# Main_Board_SW2.net
KiCad netlist of a schematic drawn in EAGLE
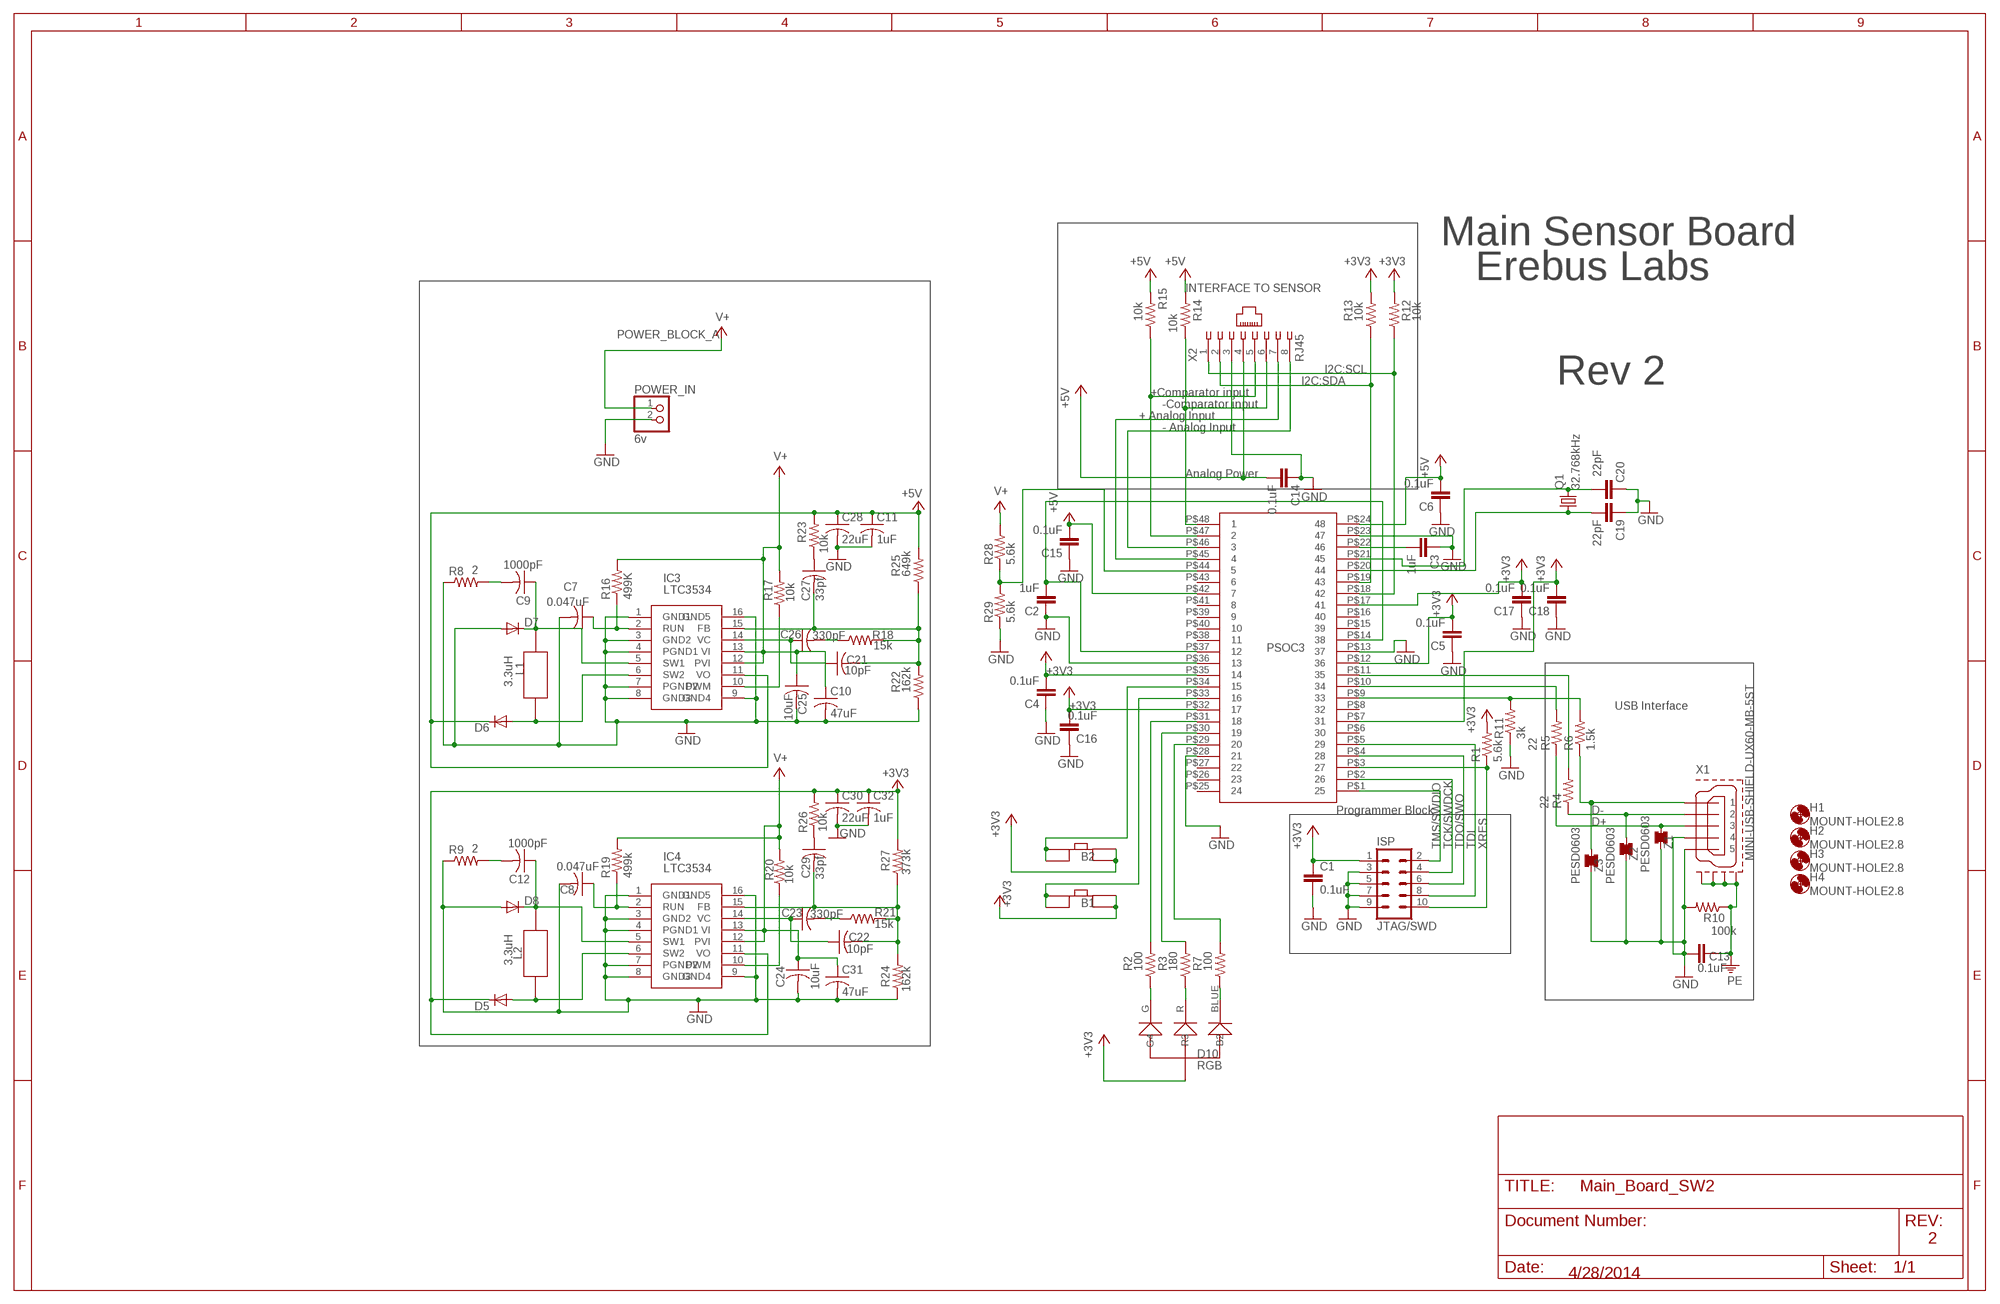
[diagram p0: schematic, sheet 1]

(export (version "E")
  (design (tool "Eeschema 10.0.6"))
  (components
    (comp (ref "C1")
      (value "0.1uF")
      (footprint "eagle-import:C0603K")
      (libsource (lib "eagle-import") (part "C-EUC0603K"))
    )
    (comp (ref "C2")
      (value "1uF")
      (footprint "eagle-import:C0603")
      (libsource (lib "eagle-import") (part "C-EUC0603"))
    )
    (comp (ref "C3")
      (value "1uF")
      (footprint "eagle-import:C0603")
      (libsource (lib "eagle-import") (part "C-EUC0603"))
    )
    (comp (ref "C4")
      (value "0.1uF")
      (footprint "eagle-import:C0603K")
      (libsource (lib "eagle-import") (part "C-EUC0603K"))
    )
    (comp (ref "C5")
      (value "0.1uF")
      (footprint "eagle-import:C0603K")
      (libsource (lib "eagle-import") (part "C-EUC0603K"))
    )
    (comp (ref "C6")
      (value "0.1uF")
      (footprint "eagle-import:C0603K")
      (libsource (lib "eagle-import") (part "C-EUC0603K"))
    )
    (comp (ref "C7")
      (value "0.047uF")
      (footprint "eagle-import:C0402")
      (libsource (lib "eagle-import") (part "C-USC0402"))
    )
    (comp (ref "C8")
      (value "0.047uF")
      (footprint "eagle-import:C0402")
      (libsource (lib "eagle-import") (part "C-USC0402"))
    )
    (comp (ref "C9")
      (value "1000pF")
      (footprint "eagle-import:C0402")
      (libsource (lib "eagle-import") (part "C-USC0402"))
    )
    (comp (ref "C10")
      (value "47uF")
      (footprint "eagle-import:C1210")
      (libsource (lib "eagle-import") (part "C-USC1210"))
    )
    (comp (ref "C11")
      (value "1uF")
      (footprint "eagle-import:C0603")
      (libsource (lib "eagle-import") (part "C-USC0603"))
    )
    (comp (ref "C12")
      (value "1000pF")
      (footprint "eagle-import:C0402")
      (libsource (lib "eagle-import") (part "C-USC0402"))
    )
    (comp (ref "C13")
      (value "0.1uF")
      (footprint "eagle-import:C0603K")
      (libsource (lib "eagle-import") (part "C-EUC0603K"))
    )
    (comp (ref "C14")
      (value "0.1uF")
      (footprint "eagle-import:C0603K")
      (libsource (lib "eagle-import") (part "C-EUC0603K"))
    )
    (comp (ref "C15")
      (value "0.1uF")
      (footprint "eagle-import:C0603K")
      (libsource (lib "eagle-import") (part "C-EUC0603K"))
    )
    (comp (ref "C16")
      (value "0.1uF")
      (footprint "eagle-import:C0603K")
      (libsource (lib "eagle-import") (part "C-EUC0603K"))
    )
    (comp (ref "C17")
      (value "0.1uF")
      (footprint "eagle-import:C0603K")
      (libsource (lib "eagle-import") (part "C-EUC0603K"))
    )
    (comp (ref "C18")
      (value "0.1uF")
      (footprint "eagle-import:C0603K")
      (libsource (lib "eagle-import") (part "C-EUC0603K"))
    )
    (comp (ref "C19")
      (value "22pF")
      (footprint "eagle-import:C0603")
      (libsource (lib "eagle-import") (part "C-EUC0603"))
    )
    (comp (ref "C20")
      (value "22pF")
      (footprint "eagle-import:C0603")
      (libsource (lib "eagle-import") (part "C-EUC0603"))
    )
    (comp (ref "C21")
      (value "10pF")
      (footprint "eagle-import:C0805")
      (libsource (lib "eagle-import") (part "C-USC0805"))
    )
    (comp (ref "C22")
      (value "10pF")
      (footprint "eagle-import:C0805")
      (libsource (lib "eagle-import") (part "C-USC0805"))
    )
    (comp (ref "C23")
      (value "330pF")
      (footprint "eagle-import:C0805")
      (libsource (lib "eagle-import") (part "C-USC0805"))
    )
    (comp (ref "C24")
      (value "10uF")
      (footprint "eagle-import:C0805")
      (libsource (lib "eagle-import") (part "C-USC0805"))
    )
    (comp (ref "C25")
      (value "10uF")
      (footprint "eagle-import:C0805")
      (libsource (lib "eagle-import") (part "C-USC0805"))
    )
    (comp (ref "C26")
      (value "330pF")
      (footprint "eagle-import:C0805")
      (libsource (lib "eagle-import") (part "C-USC0805"))
    )
    (comp (ref "C27")
      (value "33pf")
      (footprint "eagle-import:C0805")
      (libsource (lib "eagle-import") (part "C-USC0805"))
    )
    (comp (ref "C28")
      (value "22uF")
      (footprint "eagle-import:C0805")
      (libsource (lib "eagle-import") (part "C-USC0805"))
    )
    (comp (ref "C29")
      (value "33pf")
      (footprint "eagle-import:C0805")
      (libsource (lib "eagle-import") (part "C-USC0805"))
    )
    (comp (ref "C30")
      (value "22uF")
      (footprint "eagle-import:C0805")
      (libsource (lib "eagle-import") (part "C-USC0805"))
    )
    (comp (ref "C31")
      (value "47uF")
      (footprint "eagle-import:C1210")
      (libsource (lib "eagle-import") (part "C-USC1210"))
    )
    (comp (ref "C32")
      (value "1uF")
      (footprint "eagle-import:C0603")
      (libsource (lib "eagle-import") (part "C-USC0603"))
    )
    (comp (ref "D5")
      (value "DIODE-SOD323-R")
      (footprint "eagle-import:SOD323-R")
      (libsource (lib "eagle-import") (part "DIODE-SOD323-R"))
    )
    (comp (ref "D6")
      (value "DIODE-SOD323-R")
      (footprint "eagle-import:SOD323-R")
      (libsource (lib "eagle-import") (part "DIODE-SOD323-R"))
    )
    (comp (ref "D7")
      (value "DIODE-SOD323-R")
      (footprint "eagle-import:SOD323-R")
      (libsource (lib "eagle-import") (part "DIODE-SOD323-R"))
    )
    (comp (ref "D8")
      (value "DIODE-SOD323-R")
      (footprint "eagle-import:SOD323-R")
      (libsource (lib "eagle-import") (part "DIODE-SOD323-R"))
    )
    (comp (ref "H1")
      (value "MOUNT-HOLE2.8")
      (footprint "eagle-import:2,8")
      (libsource (lib "eagle-import") (part "MOUNT-HOLE2.8"))
    )
    (comp (ref "H2")
      (value "MOUNT-HOLE2.8")
      (footprint "eagle-import:2,8")
      (libsource (lib "eagle-import") (part "MOUNT-HOLE2.8"))
    )
    (comp (ref "H3")
      (value "MOUNT-HOLE2.8")
      (footprint "eagle-import:2,8")
      (libsource (lib "eagle-import") (part "MOUNT-HOLE2.8"))
    )
    (comp (ref "H4")
      (value "MOUNT-HOLE2.8")
      (footprint "eagle-import:2,8")
      (libsource (lib "eagle-import") (part "MOUNT-HOLE2.8"))
    )
    (comp (ref "IC3")
      (value "SWITCHER")
      (footprint "eagle-import:SSOP16")
      (libsource (lib "eagle-import") (part "SWITCHER"))
    )
    (comp (ref "IC4")
      (value "SWITCHER")
      (footprint "eagle-import:SSOP16")
      (libsource (lib "eagle-import") (part "SWITCHER"))
    )
    (comp (ref "ISP")
      (value "JTAG/SWD")
      (footprint "eagle-import:FTSH-105-01-L-DV-K")
      (libsource (lib "eagle-import") (part "FTSH-105-01-L-DV-K"))
    )
    (comp (ref "L1")
      (value "3.3uH")
      (footprint "eagle-import:SHEILDED_COIL")
      (libsource (lib "eagle-import") (part "SHEILDED_COIL"))
    )
    (comp (ref "L2")
      (value "4.7uH")
      (footprint "eagle-import:SHEILDED_COIL")
      (libsource (lib "eagle-import") (part "SHEILDED_COIL"))
    )
    (comp (ref "POWER_IN")
      (value "6v")
      (footprint "eagle-import:1X02")
      (libsource (lib "eagle-import") (part "PINHD-1X2"))
    )
    (comp (ref "Q1")
      (value "32.768kHz")
      (footprint "eagle-import:TC38H")
      (libsource (lib "eagle-import") (part "CRYSTALTC38H"))
    )
    (comp (ref "R1")
      (value "5.6k")
      (footprint "eagle-import:R0805")
      (libsource (lib "eagle-import") (part "R-US_R0805"))
    )
    (comp (ref "R2")
      (value "100")
      (footprint "eagle-import:R0805")
      (libsource (lib "eagle-import") (part "R-US_R0805"))
    )
    (comp (ref "R3")
      (value "180")
      (footprint "eagle-import:R0805")
      (libsource (lib "eagle-import") (part "R-US_R0805"))
    )
    (comp (ref "R4")
      (value "22")
      (footprint "eagle-import:R0603")
      (libsource (lib "eagle-import") (part "R-US_R0603"))
    )
    (comp (ref "R5")
      (value "22")
      (footprint "eagle-import:R0603")
      (libsource (lib "eagle-import") (part "R-US_R0603"))
    )
    (comp (ref "R6")
      (value "1.5k")
      (footprint "eagle-import:R0805")
      (libsource (lib "eagle-import") (part "R-US_R0805"))
    )
    (comp (ref "R7")
      (value "100")
      (footprint "eagle-import:R0805")
      (libsource (lib "eagle-import") (part "R-US_R0805"))
    )
    (comp (ref "R8")
      (value "2")
      (footprint "eagle-import:R0402")
      (libsource (lib "eagle-import") (part "R-US_R0402"))
    )
    (comp (ref "R9")
      (value "2")
      (footprint "eagle-import:R0402")
      (libsource (lib "eagle-import") (part "R-US_R0402"))
    )
    (comp (ref "R10")
      (value "100k")
      (footprint "eagle-import:R0805")
      (libsource (lib "eagle-import") (part "R-US_R0805"))
    )
    (comp (ref "R11")
      (value "3k")
      (footprint "eagle-import:R0805")
      (libsource (lib "eagle-import") (part "R-US_R0805"))
    )
    (comp (ref "R12")
      (value "10k")
      (footprint "eagle-import:R0805")
      (libsource (lib "eagle-import") (part "R-US_R0805"))
    )
    (comp (ref "R13")
      (value "10k")
      (footprint "eagle-import:R0805")
      (libsource (lib "eagle-import") (part "R-US_R0805"))
    )
    (comp (ref "R14")
      (value "10k")
      (footprint "eagle-import:R0805")
      (libsource (lib "eagle-import") (part "R-US_R0805"))
    )
    (comp (ref "R15")
      (value "10k")
      (footprint "eagle-import:R0805")
      (libsource (lib "eagle-import") (part "R-US_R0805"))
    )
    (comp (ref "R16")
      (value "499K")
      (footprint "eagle-import:R0805")
      (libsource (lib "eagle-import") (part "resistor_R-US_R0805"))
    )
    (comp (ref "R17")
      (value "10k")
      (footprint "eagle-import:R0805")
      (libsource (lib "eagle-import") (part "R-US_R0805"))
    )
    (comp (ref "R18")
      (value "15k")
      (footprint "eagle-import:R0805")
      (libsource (lib "eagle-import") (part "R-US_R0805"))
    )
    (comp (ref "R19")
      (value "499k")
      (footprint "eagle-import:R0805")
      (libsource (lib "eagle-import") (part "resistor_R-US_R0805"))
    )
    (comp (ref "R20")
      (value "10k")
      (footprint "eagle-import:R0805")
      (libsource (lib "eagle-import") (part "R-US_R0805"))
    )
    (comp (ref "R21")
      (value "15k")
      (footprint "eagle-import:R0805")
      (libsource (lib "eagle-import") (part "R-US_R0805"))
    )
    (comp (ref "R22")
      (value "162k")
      (footprint "eagle-import:R0805")
      (libsource (lib "eagle-import") (part "R-US_R0805"))
    )
    (comp (ref "R23")
      (value "10k")
      (footprint "eagle-import:R0805")
      (libsource (lib "eagle-import") (part "R-US_R0805"))
    )
    (comp (ref "R24")
      (value "162k")
      (footprint "eagle-import:R0805")
      (libsource (lib "eagle-import") (part "R-US_R0805"))
    )
    (comp (ref "R25")
      (value "649k")
      (footprint "eagle-import:R0805")
      (libsource (lib "eagle-import") (part "R-US_R0805"))
    )
    (comp (ref "R26")
      (value "10k")
      (footprint "eagle-import:R0805")
      (libsource (lib "eagle-import") (part "R-US_R0805"))
    )
    (comp (ref "R27")
      (value "373k")
      (footprint "eagle-import:R0805")
      (libsource (lib "eagle-import") (part "R-US_R0805"))
    )
    (comp (ref "R28")
      (value "5.6k")
      (footprint "eagle-import:R0805")
      (libsource (lib "eagle-import") (part "R-US_R0805"))
    )
    (comp (ref "R29")
      (value "5.6k")
      (footprint "eagle-import:R0805")
      (libsource (lib "eagle-import") (part "R-US_R0805"))
    )
    (comp (ref "RGB_LED")
      (value "RGB_LED")
      (footprint "eagle-import:RGB_LED")
      (libsource (lib "eagle-import") (part "RGB_LED"))
    )
    (comp (ref "U$1")
      (value "PSOC_3_48PIN_SSOP")
      (footprint "eagle-import:PSOC_3_48PIN_SSOP")
      (libsource (lib "eagle-import") (part "PSOC_3_48PIN_SSOP"))
    )
    (comp (ref "U$5")
      (value "SPST")
      (footprint "eagle-import:SPST")
      (libsource (lib "eagle-import") (part "SPST"))
    )
    (comp (ref "U$6")
      (value "SPST")
      (footprint "eagle-import:SPST")
      (libsource (lib "eagle-import") (part "SPST"))
    )
    (comp (ref "X1")
      (value "MINI-USB-SHIELD-UX60-MB-5ST")
      (footprint "eagle-import:UX60-MB-5ST")
      (libsource (lib "eagle-import") (part "MINI-USB-SHIELD-UX60-MB-5ST"))
    )
    (comp (ref "X2")
      (value "RJ45")
      (footprint "eagle-import:555167-1")
      (libsource (lib "eagle-import") (part "555167-1"))
    )
    (comp (ref "Z1")
      (value "PESD0603")
      (footprint "eagle-import:SMD-0603")
      (libsource (lib "eagle-import") (part "PESD0603"))
    )
    (comp (ref "Z2")
      (value "PESD0603")
      (footprint "eagle-import:SMD-0603")
      (libsource (lib "eagle-import") (part "PESD0603"))
    )
    (comp (ref "Z3")
      (value "PESD0603")
      (footprint "eagle-import:SMD-0603")
      (libsource (lib "eagle-import") (part "PESD0603"))
    )
  )
  (nets
    (net (code "1") (name "+3V3") (class "Default")
      (node (ref "C1") (pin "1") (pinfunction "1_1") (pintype "passive"))
      (node (ref "C16") (pin "2") (pinfunction "2_2") (pintype "passive"))
      (node (ref "C17") (pin "2") (pinfunction "2_2") (pintype "passive"))
      (node (ref "C18") (pin "2") (pinfunction "2_2") (pintype "passive"))
      (node (ref "C30") (pin "1") (pinfunction "1_1") (pintype "passive"))
      (node (ref "C32") (pin "1") (pinfunction "1_1") (pintype "passive"))
      (node (ref "C4") (pin "2") (pinfunction "2_2") (pintype "passive"))
      (node (ref "C5") (pin "2") (pinfunction "2_2") (pintype "passive"))
      (node (ref "D5") (pin "C") (pinfunction "C_C") (pintype "passive"))
      (node (ref "IC4") (pin "11") (pinfunction "VO_11") (pintype "bidirectional"))
      (node (ref "ISP") (pin "1") (pinfunction "1_1") (pintype "passive"))
      (node (ref "R1") (pin "2") (pinfunction "2_2") (pintype "passive"))
      (node (ref "R12") (pin "2") (pinfunction "2_2") (pintype "passive"))
      (node (ref "R13") (pin "2") (pinfunction "2_2") (pintype "passive"))
      (node (ref "R26") (pin "2") (pinfunction "2_2") (pintype "passive"))
      (node (ref "R27") (pin "2") (pinfunction "2_2") (pintype "passive"))
      (node (ref "RGB_LED") (pin "VCC") (pinfunction "VCC1_VCC") (pintype "bidirectional"))
      (node (ref "U$1") (pin "P$12") (pinfunction "36_P$12") (pintype "bidirectional"))
      (node (ref "U$1") (pin "P$17") (pinfunction "41_P$17") (pintype "bidirectional"))
      (node (ref "U$1") (pin "P$32") (pinfunction "17_P$32") (pintype "bidirectional"))
      (node (ref "U$1") (pin "P$35") (pinfunction "14_P$35") (pintype "bidirectional"))
      (node (ref "U$1") (pin "P$7") (pinfunction "31_P$7") (pintype "bidirectional"))
      (node (ref "U$5") (pin "B1") (pinfunction "B1_B1") (pintype "bidirectional"))
      (node (ref "U$5") (pin "B2") (pinfunction "B2_B2") (pintype "bidirectional"))
      (node (ref "U$6") (pin "B1") (pinfunction "B1_B1") (pintype "bidirectional"))
      (node (ref "U$6") (pin "B2") (pinfunction "B2_B2") (pintype "bidirectional"))
    )
    (net (code "2") (name "+5V") (class "Default")
      (node (ref "C11") (pin "1") (pinfunction "1_1") (pintype "passive"))
      (node (ref "C14") (pin "2") (pinfunction "2_2") (pintype "passive"))
      (node (ref "C15") (pin "2") (pinfunction "2_2") (pintype "passive"))
      (node (ref "C28") (pin "1") (pinfunction "1_1") (pintype "passive"))
      (node (ref "C6") (pin "2") (pinfunction "2_2") (pintype "passive"))
      (node (ref "D6") (pin "C") (pinfunction "C_C") (pintype "passive"))
      (node (ref "IC3") (pin "11") (pinfunction "VO_11") (pintype "bidirectional"))
      (node (ref "R14") (pin "2") (pinfunction "2_2") (pintype "passive"))
      (node (ref "R15") (pin "2") (pinfunction "2_2") (pintype "passive"))
      (node (ref "R23") (pin "2") (pinfunction "2_2") (pintype "passive"))
      (node (ref "R25") (pin "2") (pinfunction "2_2") (pintype "passive"))
      (node (ref "U$1") (pin "P$24") (pinfunction "48_P$24") (pintype "bidirectional"))
      (node (ref "U$1") (pin "P$42") (pinfunction "7_P$42") (pintype "bidirectional"))
      (node (ref "X2") (pin "4") (pinfunction "4_4") (pintype "passive"))
    )
    (net (code "3") (name "GND") (class "Default")
      (node (ref "C1") (pin "2") (pinfunction "2_2") (pintype "passive"))
      (node (ref "C10") (pin "2") (pinfunction "2_2") (pintype "passive"))
      (node (ref "C11") (pin "2") (pinfunction "2_2") (pintype "passive"))
      (node (ref "C13") (pin "2") (pinfunction "2_2") (pintype "passive"))
      (node (ref "C14") (pin "1") (pinfunction "1_1") (pintype "passive"))
      (node (ref "C15") (pin "1") (pinfunction "1_1") (pintype "passive"))
      (node (ref "C16") (pin "1") (pinfunction "1_1") (pintype "passive"))
      (node (ref "C17") (pin "1") (pinfunction "1_1") (pintype "passive"))
      (node (ref "C18") (pin "1") (pinfunction "1_1") (pintype "passive"))
      (node (ref "C19") (pin "1") (pinfunction "1_1") (pintype "passive"))
      (node (ref "C2") (pin "1") (pinfunction "1_1") (pintype "passive"))
      (node (ref "C20") (pin "1") (pinfunction "1_1") (pintype "passive"))
      (node (ref "C24") (pin "2") (pinfunction "2_2") (pintype "passive"))
      (node (ref "C25") (pin "2") (pinfunction "2_2") (pintype "passive"))
      (node (ref "C28") (pin "2") (pinfunction "2_2") (pintype "passive"))
      (node (ref "C3") (pin "1") (pinfunction "1_1") (pintype "passive"))
      (node (ref "C30") (pin "2") (pinfunction "2_2") (pintype "passive"))
      (node (ref "C31") (pin "2") (pinfunction "2_2") (pintype "passive"))
      (node (ref "C32") (pin "2") (pinfunction "2_2") (pintype "passive"))
      (node (ref "C4") (pin "1") (pinfunction "1_1") (pintype "passive"))
      (node (ref "C5") (pin "1") (pinfunction "1_1") (pintype "passive"))
      (node (ref "C6") (pin "1") (pinfunction "1_1") (pintype "passive"))
      (node (ref "C7") (pin "2") (pinfunction "2_2") (pintype "passive"))
      (node (ref "C8") (pin "2") (pinfunction "2_2") (pintype "passive"))
      (node (ref "D7") (pin "A") (pinfunction "A_A") (pintype "passive"))
      (node (ref "D8") (pin "A") (pinfunction "A_A") (pintype "passive"))
      (node (ref "IC3") (pin "1") (pinfunction "GND1_1") (pintype "bidirectional"))
      (node (ref "IC3") (pin "16") (pinfunction "GND5_16") (pintype "bidirectional"))
      (node (ref "IC3") (pin "3") (pinfunction "GND2_3") (pintype "bidirectional"))
      (node (ref "IC3") (pin "4") (pinfunction "PGND1_4") (pintype "bidirectional"))
      (node (ref "IC3") (pin "7") (pinfunction "PGND2_7") (pintype "bidirectional"))
      (node (ref "IC3") (pin "8") (pinfunction "GND3_8") (pintype "bidirectional"))
      (node (ref "IC3") (pin "9") (pinfunction "GND4_9") (pintype "bidirectional"))
      (node (ref "IC4") (pin "1") (pinfunction "GND1_1") (pintype "bidirectional"))
      (node (ref "IC4") (pin "16") (pinfunction "GND5_16") (pintype "bidirectional"))
      (node (ref "IC4") (pin "3") (pinfunction "GND2_3") (pintype "bidirectional"))
      (node (ref "IC4") (pin "4") (pinfunction "PGND1_4") (pintype "bidirectional"))
      (node (ref "IC4") (pin "7") (pinfunction "PGND2_7") (pintype "bidirectional"))
      (node (ref "IC4") (pin "8") (pinfunction "GND3_8") (pintype "bidirectional"))
      (node (ref "IC4") (pin "9") (pinfunction "GND4_9") (pintype "bidirectional"))
      (node (ref "ISP") (pin "3") (pinfunction "3_3") (pintype "passive"))
      (node (ref "ISP") (pin "5") (pinfunction "5_5") (pintype "passive"))
      (node (ref "ISP") (pin "7") (pinfunction "7_7") (pintype "passive"))
      (node (ref "ISP") (pin "9") (pinfunction "9_9") (pintype "passive"))
      (node (ref "POWER_IN") (pin "2") (pinfunction "2_2") (pintype "passive"))
      (node (ref "R10") (pin "2") (pinfunction "2_2") (pintype "passive"))
      (node (ref "R11") (pin "1") (pinfunction "1_1") (pintype "passive"))
      (node (ref "R22") (pin "1") (pinfunction "1_1") (pintype "passive"))
      (node (ref "R24") (pin "1") (pinfunction "1_1") (pintype "passive"))
      (node (ref "R29") (pin "1") (pinfunction "1_1") (pintype "passive"))
      (node (ref "R8") (pin "1") (pinfunction "1_1") (pintype "passive"))
      (node (ref "R9") (pin "1") (pinfunction "1_1") (pintype "passive"))
      (node (ref "U$1") (pin "P$13") (pinfunction "37_P$13") (pintype "bidirectional"))
      (node (ref "U$1") (pin "P$23") (pinfunction "47_P$23") (pintype "bidirectional"))
      (node (ref "U$1") (pin "P$28") (pinfunction "21_P$28") (pintype "bidirectional"))
      (node (ref "U$1") (pin "P$36") (pinfunction "13_P$36") (pintype "bidirectional"))
      (node (ref "X1") (pin "4") (pinfunction "4_4") (pintype "input"))
      (node (ref "X1") (pin "5") (pinfunction "5_5") (pintype "input"))
      (node (ref "X2") (pin "3") (pinfunction "3_3") (pintype "passive"))
      (node (ref "Z1") (pin "1") (pinfunction "1_1") (pintype "passive"))
      (node (ref "Z2") (pin "1") (pinfunction "1_1") (pintype "passive"))
      (node (ref "Z3") (pin "1") (pinfunction "1_1") (pintype "passive"))
    )
    (net (code "4") (name "Net-(C9-Pad2)") (class "Default")
      (node (ref "C9") (pin "2") (pinfunction "2_2") (pintype "passive"))
      (node (ref "R8") (pin "2") (pinfunction "2_2") (pintype "passive"))
    )
    (net (code "5") (name "Net-(C12-Pad2)") (class "Default")
      (node (ref "C12") (pin "2") (pinfunction "2_2") (pintype "passive"))
      (node (ref "R9") (pin "2") (pinfunction "2_2") (pintype "passive"))
    )
    (net (code "6") (name "Net-(C23-Pad2)") (class "Default")
      (node (ref "C23") (pin "2") (pinfunction "2_2") (pintype "passive"))
      (node (ref "R21") (pin "1") (pinfunction "1_1") (pintype "passive"))
    )
    (net (code "7") (name "Net-(C26-Pad2)") (class "Default")
      (node (ref "C26") (pin "2") (pinfunction "2_2") (pintype "passive"))
      (node (ref "R18") (pin "1") (pinfunction "1_1") (pintype "passive"))
    )
    (net (code "8") (name "Net-(C27-Pad1)") (class "Default")
      (node (ref "C27") (pin "1") (pinfunction "1_1") (pintype "passive"))
      (node (ref "R23") (pin "1") (pinfunction "1_1") (pintype "passive"))
    )
    (net (code "9") (name "Net-(C29-Pad1)") (class "Default")
      (node (ref "C29") (pin "1") (pinfunction "1_1") (pintype "passive"))
      (node (ref "R26") (pin "1") (pinfunction "1_1") (pintype "passive"))
    )
    (net (code "10") (name "Net-(IC3-FB)") (class "Default")
      (node (ref "C21") (pin "2") (pinfunction "2_2") (pintype "passive"))
      (node (ref "C27") (pin "2") (pinfunction "2_2") (pintype "passive"))
      (node (ref "IC3") (pin "15") (pinfunction "FB_15") (pintype "bidirectional"))
      (node (ref "R18") (pin "2") (pinfunction "2_2") (pintype "passive"))
      (node (ref "R22") (pin "2") (pinfunction "2_2") (pintype "passive"))
      (node (ref "R25") (pin "1") (pinfunction "1_1") (pintype "passive"))
    )
    (net (code "11") (name "Net-(IC3-PWM)") (class "Default")
      (node (ref "IC3") (pin "10") (pinfunction "PWM_10") (pintype "bidirectional"))
      (node (ref "R17") (pin "1") (pinfunction "1_1") (pintype "passive"))
    )
    (net (code "12") (name "Net-(IC3-RUN)") (class "Default")
      (node (ref "C7") (pin "1") (pinfunction "1_1") (pintype "passive"))
      (node (ref "IC3") (pin "2") (pinfunction "RUN_2") (pintype "bidirectional"))
      (node (ref "R16") (pin "1") (pinfunction "1_1") (pintype "passive"))
    )
    (net (code "13") (name "Net-(IC3-SW1)") (class "Default")
      (node (ref "C9") (pin "1") (pinfunction "1_1") (pintype "passive"))
      (node (ref "D7") (pin "C") (pinfunction "C_C") (pintype "passive"))
      (node (ref "IC3") (pin "5") (pinfunction "SW1_5") (pintype "bidirectional"))
      (node (ref "L1") (pin "P$2") (pinfunction "P$2_P$2") (pintype "bidirectional"))
    )
    (net (code "14") (name "Net-(IC3-SW2)") (class "Default")
      (node (ref "D6") (pin "A") (pinfunction "A_A") (pintype "passive"))
      (node (ref "IC3") (pin "6") (pinfunction "SW2_6") (pintype "bidirectional"))
      (node (ref "L1") (pin "P$1") (pinfunction "P$1_P$1") (pintype "bidirectional"))
    )
    (net (code "15") (name "Net-(IC3-VC)") (class "Default")
      (node (ref "C21") (pin "1") (pinfunction "1_1") (pintype "passive"))
      (node (ref "C26") (pin "1") (pinfunction "1_1") (pintype "passive"))
      (node (ref "IC3") (pin "14") (pinfunction "VC_14") (pintype "bidirectional"))
    )
    (net (code "16") (name "Net-(IC4-FB)") (class "Default")
      (node (ref "C22") (pin "2") (pinfunction "2_2") (pintype "passive"))
      (node (ref "C29") (pin "2") (pinfunction "2_2") (pintype "passive"))
      (node (ref "IC4") (pin "15") (pinfunction "FB_15") (pintype "bidirectional"))
      (node (ref "R21") (pin "2") (pinfunction "2_2") (pintype "passive"))
      (node (ref "R24") (pin "2") (pinfunction "2_2") (pintype "passive"))
      (node (ref "R27") (pin "1") (pinfunction "1_1") (pintype "passive"))
    )
    (net (code "17") (name "Net-(IC4-PWM)") (class "Default")
      (node (ref "IC4") (pin "10") (pinfunction "PWM_10") (pintype "bidirectional"))
      (node (ref "R20") (pin "1") (pinfunction "1_1") (pintype "passive"))
    )
    (net (code "18") (name "Net-(IC4-RUN)") (class "Default")
      (node (ref "C8") (pin "1") (pinfunction "1_1") (pintype "passive"))
      (node (ref "IC4") (pin "2") (pinfunction "RUN_2") (pintype "bidirectional"))
      (node (ref "R19") (pin "1") (pinfunction "1_1") (pintype "passive"))
    )
    (net (code "19") (name "Net-(IC4-SW1)") (class "Default")
      (node (ref "C12") (pin "1") (pinfunction "1_1") (pintype "passive"))
      (node (ref "D8") (pin "C") (pinfunction "C_C") (pintype "passive"))
      (node (ref "IC4") (pin "5") (pinfunction "SW1_5") (pintype "bidirectional"))
      (node (ref "L2") (pin "P$2") (pinfunction "P$2_P$2") (pintype "bidirectional"))
    )
    (net (code "20") (name "Net-(IC4-SW2)") (class "Default")
      (node (ref "D5") (pin "A") (pinfunction "A_A") (pintype "passive"))
      (node (ref "IC4") (pin "6") (pinfunction "SW2_6") (pintype "bidirectional"))
      (node (ref "L2") (pin "P$1") (pinfunction "P$1_P$1") (pintype "bidirectional"))
    )
    (net (code "21") (name "Net-(IC4-VC)") (class "Default")
      (node (ref "C22") (pin "1") (pinfunction "1_1") (pintype "passive"))
      (node (ref "C23") (pin "1") (pinfunction "1_1") (pintype "passive"))
      (node (ref "IC4") (pin "14") (pinfunction "VC_14") (pintype "bidirectional"))
    )
    (net (code "22") (name "Net-(R4-Pad1)") (class "Default")
      (node (ref "R4") (pin "1") (pinfunction "1_1") (pintype "passive"))
      (node (ref "X1") (pin "2") (pinfunction "2_2") (pintype "input"))
      (node (ref "Z2") (pin "2") (pinfunction "2_2") (pintype "passive"))
    )
    (net (code "23") (name "Net-(R5-Pad1)") (class "Default")
      (node (ref "R5") (pin "1") (pinfunction "1_1") (pintype "passive"))
      (node (ref "X1") (pin "3") (pinfunction "3_3") (pintype "input"))
      (node (ref "Z1") (pin "2") (pinfunction "2_2") (pintype "passive"))
    )
    (net (code "24") (name "Net-(R6-Pad1)") (class "Default")
      (node (ref "R6") (pin "1") (pinfunction "1_1") (pintype "passive"))
      (node (ref "X1") (pin "1") (pinfunction "1_1") (pintype "input"))
      (node (ref "Z3") (pin "2") (pinfunction "2_2") (pintype "passive"))
    )
    (net (code "25") (name "Net-(RGB_LED-B2)") (class "Default")
      (node (ref "R7") (pin "1") (pinfunction "1_1") (pintype "passive"))
      (node (ref "RGB_LED") (pin "BLUE") (pinfunction "B2_BLUE") (pintype "bidirectional"))
    )
    (net (code "26") (name "Net-(RGB_LED-G4)") (class "Default")
      (node (ref "R2") (pin "1") (pinfunction "1_1") (pintype "passive"))
      (node (ref "RGB_LED") (pin "G") (pinfunction "G4_G") (pintype "bidirectional"))
    )
    (net (code "27") (name "Net-(RGB_LED-R3)") (class "Default")
      (node (ref "R3") (pin "1") (pinfunction "1_1") (pintype "passive"))
      (node (ref "RGB_LED") (pin "R") (pinfunction "R3_R") (pintype "bidirectional"))
    )
    (net (code "28") (name "Net-(U$1-1)") (class "Default")
      (node (ref "R14") (pin "1") (pinfunction "1_1") (pintype "passive"))
      (node (ref "U$1") (pin "P$48") (pinfunction "1_P$48") (pintype "bidirectional"))
      (node (ref "X2") (pin "6") (pinfunction "6_6") (pintype "passive"))
    )
    (net (code "29") (name "Net-(U$1-2)") (class "Default")
      (node (ref "R15") (pin "1") (pinfunction "1_1") (pintype "passive"))
      (node (ref "U$1") (pin "P$47") (pinfunction "2_P$47") (pintype "bidirectional"))
      (node (ref "X2") (pin "5") (pinfunction "5_5") (pintype "passive"))
    )
    (net (code "30") (name "Net-(U$1-3)") (class "Default")
      (node (ref "U$1") (pin "P$46") (pinfunction "3_P$46") (pintype "bidirectional"))
      (node (ref "X2") (pin "8") (pinfunction "8_8") (pintype "passive"))
    )
    (net (code "31") (name "Net-(U$1-4)") (class "Default")
      (node (ref "U$1") (pin "P$45") (pinfunction "4_P$45") (pintype "bidirectional"))
      (node (ref "X2") (pin "7") (pinfunction "7_7") (pintype "passive"))
    )
    (net (code "32") (name "Net-(U$1-5)") (class "Default")
      (node (ref "R28") (pin "1") (pinfunction "1_1") (pintype "passive"))
      (node (ref "R29") (pin "2") (pinfunction "2_2") (pintype "passive"))
      (node (ref "U$1") (pin "P$44") (pinfunction "5_P$44") (pintype "bidirectional"))
    )
    (net (code "33") (name "Net-(U$1-12)") (class "Default")
      (node (ref "C2") (pin "2") (pinfunction "2_2") (pintype "passive"))
      (node (ref "U$1") (pin "P$14") (pinfunction "38_P$14") (pintype "bidirectional"))
      (node (ref "U$1") (pin "P$37") (pinfunction "12_P$37") (pintype "bidirectional"))
    )
    (net (code "34") (name "Net-(U$1-15)") (class "Default")
      (node (ref "U$1") (pin "P$34") (pinfunction "15_P$34") (pintype "bidirectional"))
      (node (ref "U$5") (pin "A1") (pinfunction "A1_A1") (pintype "bidirectional"))
      (node (ref "U$5") (pin "A2") (pinfunction "A2_A2") (pintype "bidirectional"))
    )
    (net (code "35") (name "Net-(U$1-16)") (class "Default")
      (node (ref "U$1") (pin "P$33") (pinfunction "16_P$33") (pintype "bidirectional"))
      (node (ref "U$6") (pin "A1") (pinfunction "A1_A1") (pintype "bidirectional"))
      (node (ref "U$6") (pin "A2") (pinfunction "A2_A2") (pintype "bidirectional"))
    )
    (net (code "36") (name "Net-(U$1-18)") (class "Default")
      (node (ref "R2") (pin "2") (pinfunction "2_2") (pintype "passive"))
      (node (ref "U$1") (pin "P$31") (pinfunction "18_P$31") (pintype "bidirectional"))
    )
    (net (code "37") (name "Net-(U$1-19)") (class "Default")
      (node (ref "R3") (pin "2") (pinfunction "2_2") (pintype "passive"))
      (node (ref "U$1") (pin "P$30") (pinfunction "19_P$30") (pintype "bidirectional"))
    )
    (net (code "38") (name "Net-(U$1-20)") (class "Default")
      (node (ref "R7") (pin "2") (pinfunction "2_2") (pintype "passive"))
      (node (ref "U$1") (pin "P$29") (pinfunction "20_P$29") (pintype "bidirectional"))
    )
    (net (code "39") (name "Net-(U$1-25)") (class "Default")
      (node (ref "ISP") (pin "2") (pinfunction "2_2") (pintype "passive"))
      (node (ref "U$1") (pin "P$1") (pinfunction "25_P$1") (pintype "bidirectional"))
    )
    (net (code "40") (name "Net-(U$1-26)") (class "Default")
      (node (ref "ISP") (pin "4") (pinfunction "4_4") (pintype "passive"))
      (node (ref "U$1") (pin "P$2") (pinfunction "26_P$2") (pintype "bidirectional"))
    )
    (net (code "41") (name "Net-(U$1-27)") (class "Default")
      (node (ref "ISP") (pin "10") (pinfunction "10_10") (pintype "passive"))
      (node (ref "R1") (pin "1") (pinfunction "1_1") (pintype "passive"))
      (node (ref "U$1") (pin "P$3") (pinfunction "27_P$3") (pintype "bidirectional"))
    )
    (net (code "42") (name "Net-(U$1-28)") (class "Default")
      (node (ref "ISP") (pin "6") (pinfunction "6_6") (pintype "passive"))
      (node (ref "U$1") (pin "P$4") (pinfunction "28_P$4") (pintype "bidirectional"))
    )
    (net (code "43") (name "Net-(U$1-29)") (class "Default")
      (node (ref "ISP") (pin "8") (pinfunction "8_8") (pintype "passive"))
      (node (ref "U$1") (pin "P$5") (pinfunction "29_P$5") (pintype "bidirectional"))
    )
    (net (code "44") (name "Net-(U$1-33)") (class "Default")
      (node (ref "R11") (pin "2") (pinfunction "2_2") (pintype "passive"))
      (node (ref "R6") (pin "2") (pinfunction "2_2") (pintype "passive"))
      (node (ref "U$1") (pin "P$9") (pinfunction "33_P$9") (pintype "bidirectional"))
    )
    (net (code "45") (name "Net-(U$1-34)") (class "Default")
      (node (ref "R5") (pin "2") (pinfunction "2_2") (pintype "passive"))
      (node (ref "U$1") (pin "P$10") (pinfunction "34_P$10") (pintype "bidirectional"))
    )
    (net (code "46") (name "Net-(U$1-35)") (class "Default")
      (node (ref "R4") (pin "2") (pinfunction "2_2") (pintype "passive"))
      (node (ref "U$1") (pin "P$11") (pinfunction "35_P$11") (pintype "bidirectional"))
    )
    (net (code "47") (name "Net-(U$1-42)") (class "Default")
      (node (ref "R12") (pin "1") (pinfunction "1_1") (pintype "passive"))
      (node (ref "U$1") (pin "P$18") (pinfunction "42_P$18") (pintype "bidirectional"))
      (node (ref "X2") (pin "1") (pinfunction "1_1") (pintype "passive"))
    )
    (net (code "48") (name "Net-(U$1-43)") (class "Default")
      (node (ref "R13") (pin "1") (pinfunction "1_1") (pintype "passive"))
      (node (ref "U$1") (pin "P$19") (pinfunction "43_P$19") (pintype "bidirectional"))
      (node (ref "X2") (pin "2") (pinfunction "2_2") (pintype "passive"))
    )
    (net (code "49") (name "Net-(U$1-44)") (class "Default")
      (node (ref "C19") (pin "2") (pinfunction "2_2") (pintype "passive"))
      (node (ref "Q1") (pin "1") (pinfunction "1_1") (pintype "passive"))
      (node (ref "U$1") (pin "P$20") (pinfunction "44_P$20") (pintype "bidirectional"))
    )
    (net (code "50") (name "Net-(U$1-45)") (class "Default")
      (node (ref "C20") (pin "2") (pinfunction "2_2") (pintype "passive"))
      (node (ref "Q1") (pin "2") (pinfunction "2_2") (pintype "passive"))
      (node (ref "U$1") (pin "P$21") (pinfunction "45_P$21") (pintype "bidirectional"))
    )
    (net (code "51") (name "Net-(U$1-46)") (class "Default")
      (node (ref "C3") (pin "2") (pinfunction "2_2") (pintype "passive"))
      (node (ref "U$1") (pin "P$22") (pinfunction "46_P$22") (pintype "bidirectional"))
    )
    (net (code "52") (name "PE") (class "Default")
      (node (ref "C13") (pin "1") (pinfunction "1_1") (pintype "passive"))
      (node (ref "R10") (pin "1") (pinfunction "1_1") (pintype "passive"))
      (node (ref "X1") (pin "M1") (pinfunction "GND1_M1") (pintype "bidirectional"))
      (node (ref "X1") (pin "M2") (pinfunction "GND2_M2") (pintype "bidirectional"))
      (node (ref "X1") (pin "M3") (pinfunction "GND3_M3") (pintype "bidirectional"))
      (node (ref "X1") (pin "M4") (pinfunction "GND4_M4") (pintype "bidirectional"))
    )
    (net (code "53") (name "V+") (class "Default")
      (node (ref "C10") (pin "1") (pinfunction "1_1") (pintype "passive"))
      (node (ref "C24") (pin "1") (pinfunction "1_1") (pintype "passive"))
      (node (ref "C25") (pin "1") (pinfunction "1_1") (pintype "passive"))
      (node (ref "C31") (pin "1") (pinfunction "1_1") (pintype "passive"))
      (node (ref "IC3") (pin "12") (pinfunction "PVI_12") (pintype "bidirectional"))
      (node (ref "IC3") (pin "13") (pinfunction "VI_13") (pintype "bidirectional"))
      (node (ref "IC4") (pin "12") (pinfunction "PVI_12") (pintype "bidirectional"))
      (node (ref "IC4") (pin "13") (pinfunction "VI_13") (pintype "bidirectional"))
      (node (ref "POWER_IN") (pin "1") (pinfunction "1_1") (pintype "passive"))
      (node (ref "R16") (pin "2") (pinfunction "2_2") (pintype "passive"))
      (node (ref "R17") (pin "2") (pinfunction "2_2") (pintype "passive"))
      (node (ref "R19") (pin "2") (pinfunction "2_2") (pintype "passive"))
      (node (ref "R20") (pin "2") (pinfunction "2_2") (pintype "passive"))
      (node (ref "R28") (pin "2") (pinfunction "2_2") (pintype "passive"))
    )
    (net (code "54") (name "unconnected-(U$1-6-PadP$43)") (class "Default")
      (node (ref "U$1") (pin "P$43") (pinfunction "6_P$43") (pintype "bidirectional"))
    )
    (net (code "55") (name "unconnected-(U$1-8-PadP$41)") (class "Default")
      (node (ref "U$1") (pin "P$41") (pinfunction "8_P$41") (pintype "bidirectional"))
    )
    (net (code "56") (name "unconnected-(U$1-9-PadP$39)") (class "Default")
      (node (ref "U$1") (pin "P$39") (pinfunction "9_P$39") (pintype "bidirectional"))
    )
    (net (code "57") (name "unconnected-(U$1-10-PadP$40)") (class "Default")
      (node (ref "U$1") (pin "P$40") (pinfunction "10_P$40") (pintype "bidirectional"))
    )
    (net (code "58") (name "unconnected-(U$1-11-PadP$38)") (class "Default")
      (node (ref "U$1") (pin "P$38") (pinfunction "11_P$38") (pintype "bidirectional"))
    )
    (net (code "59") (name "unconnected-(U$1-22-PadP$27)") (class "Default")
      (node (ref "U$1") (pin "P$27") (pinfunction "22_P$27") (pintype "bidirectional"))
    )
    (net (code "60") (name "unconnected-(U$1-23-PadP$26)") (class "Default")
      (node (ref "U$1") (pin "P$26") (pinfunction "23_P$26") (pintype "bidirectional"))
    )
    (net (code "61") (name "unconnected-(U$1-24-PadP$25)") (class "Default")
      (node (ref "U$1") (pin "P$25") (pinfunction "24_P$25") (pintype "bidirectional"))
    )
    (net (code "62") (name "unconnected-(U$1-30-PadP$6)") (class "Default")
      (node (ref "U$1") (pin "P$6") (pinfunction "30_P$6") (pintype "bidirectional"))
    )
    (net (code "63") (name "unconnected-(U$1-32-PadP$8)") (class "Default")
      (node (ref "U$1") (pin "P$8") (pinfunction "32_P$8") (pintype "bidirectional"))
    )
    (net (code "64") (name "unconnected-(U$1-39-PadP$15)") (class "Default")
      (node (ref "U$1") (pin "P$15") (pinfunction "39_P$15") (pintype "bidirectional"))
    )
    (net (code "65") (name "unconnected-(U$1-40-PadP$16)") (class "Default")
      (node (ref "U$1") (pin "P$16") (pinfunction "40_P$16") (pintype "bidirectional"))
    )
  )
)
